# Serial_CAN_Bus_V1_3.net
KiCad netlist of a schematic drawn in EAGLE
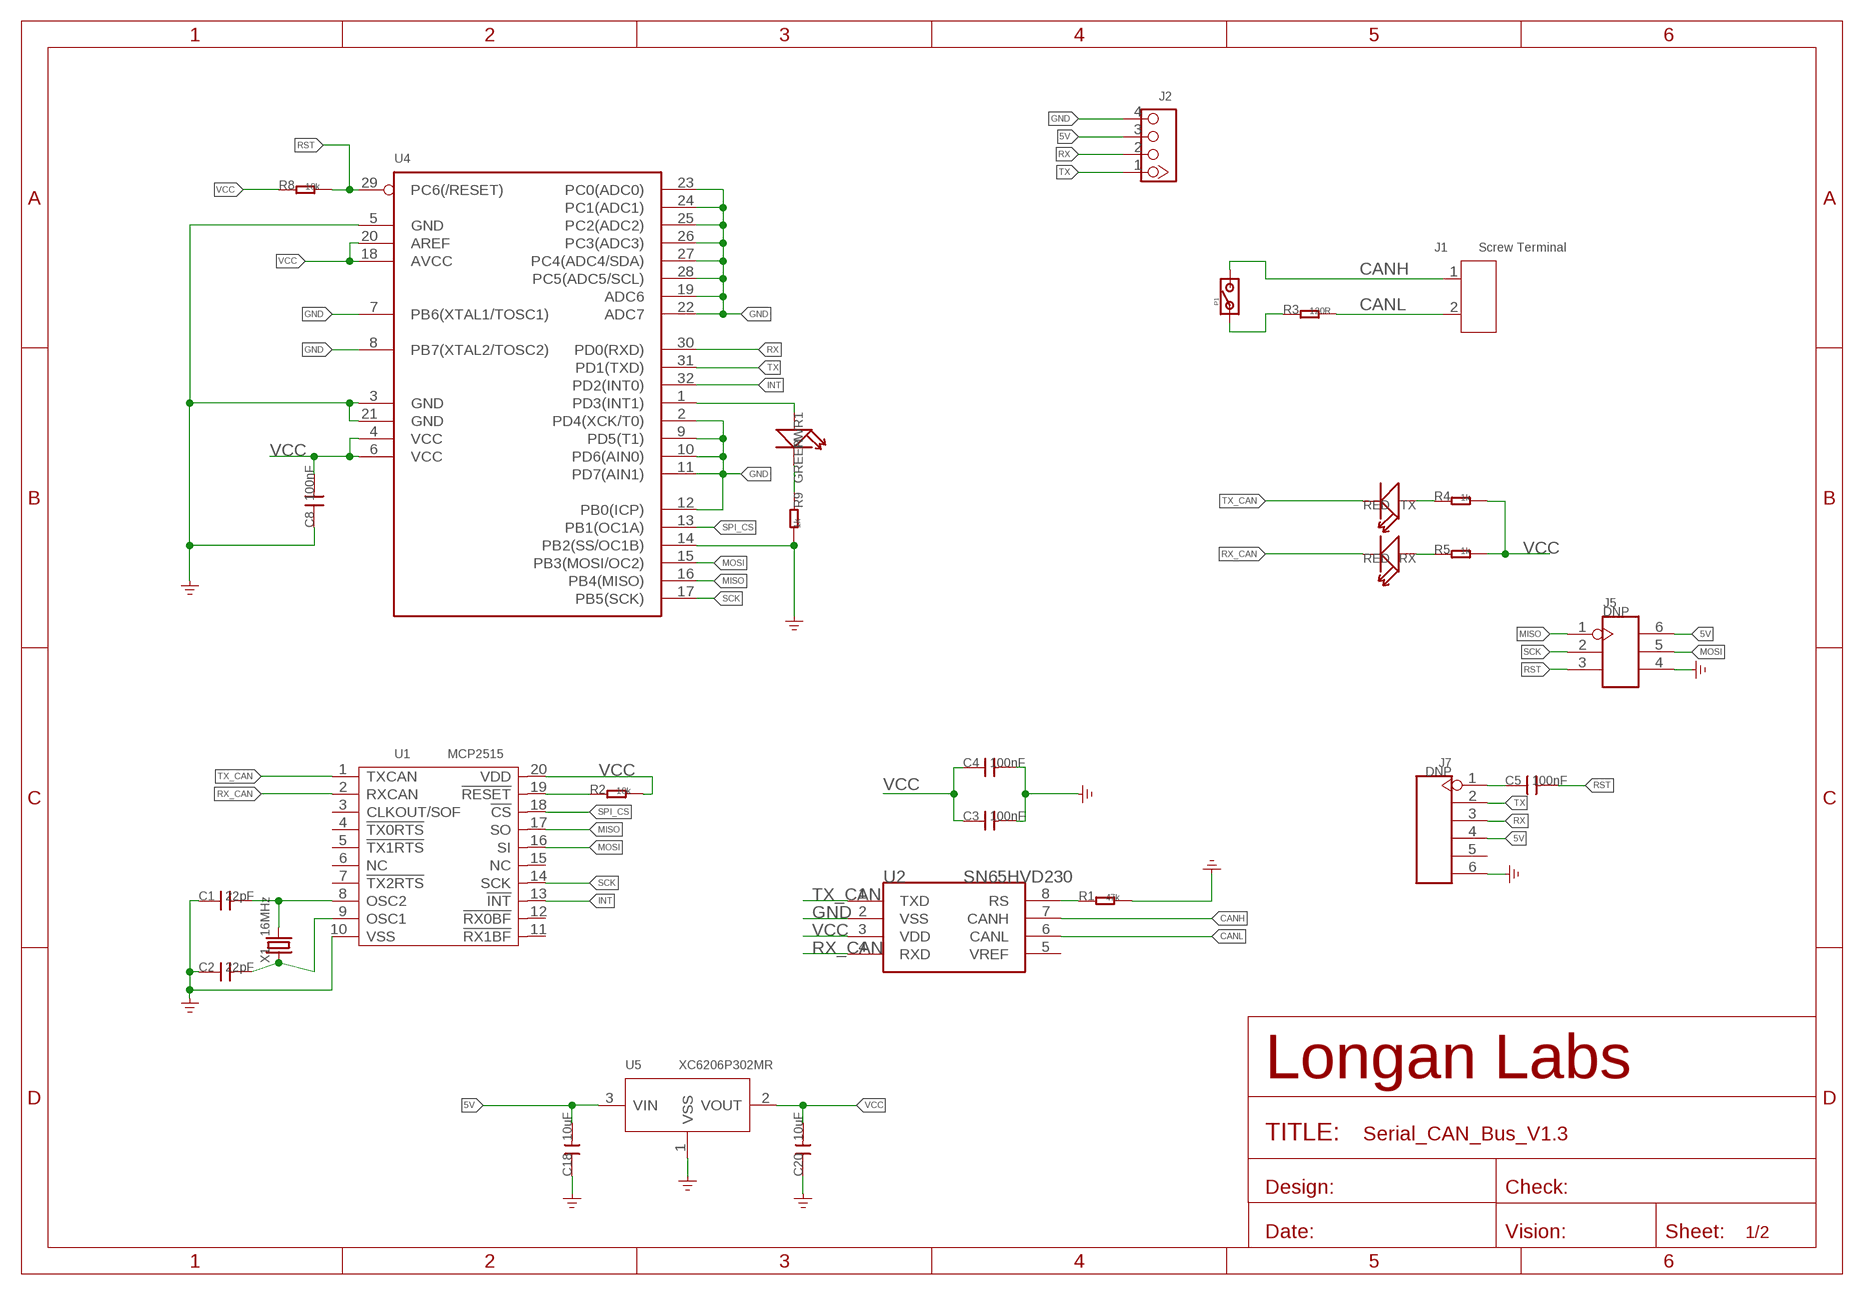
[diagram p0: schematic, sheet 1]

(export (version "E")
  (design (tool "Eeschema 10.0.6"))
  (components
    (comp (ref "C1")
      (value "22pF")
      (footprint "eagle-import:0603")
      (libsource (lib "eagle-import") (part "C-0603"))
    )
    (comp (ref "C2")
      (value "22pF")
      (footprint "eagle-import:0603")
      (libsource (lib "eagle-import") (part "C-0603"))
    )
    (comp (ref "C3")
      (value "100nF")
      (footprint "eagle-import:0603")
      (libsource (lib "eagle-import") (part "C-0603"))
    )
    (comp (ref "C4")
      (value "100nF")
      (footprint "eagle-import:0603")
      (libsource (lib "eagle-import") (part "C-0603"))
    )
    (comp (ref "C5")
      (value "100nF")
      (footprint "eagle-import:0603")
      (libsource (lib "eagle-import") (part "C-0603"))
    )
    (comp (ref "C8")
      (value "100nF")
      (footprint "eagle-import:0603")
      (libsource (lib "eagle-import") (part "C-0603"))
    )
    (comp (ref "C18")
      (value "10uF")
      (footprint "eagle-import:C0603")
      (libsource (lib "eagle-import") (part "CAP-0603"))
    )
    (comp (ref "C20")
      (value "10uF")
      (footprint "eagle-import:C0603")
      (libsource (lib "eagle-import") (part "CAP-0603"))
    )
    (comp (ref "J1")
      (value "Screw Terminal")
      (footprint "eagle-import:2P-3.5")
      (libsource (lib "eagle-import") (part "SCREW-TERMINAL-2P'3.5'"))
    )
    (comp (ref "J2")
      (value "320110033")
      (footprint "eagle-import:HW4-2.0")
      (libsource (lib "eagle-import") (part "GROVE-CONNECTOR-DIP-2.0"))
    )
    (comp (ref "J5")
      (value "DNP")
      (footprint "eagle-import:H2X3-SMD-2.0(1.143)")
      (libsource (lib "eagle-import") (part "HEADER-2X3P-2.0-1.143"))
    )
    (comp (ref "J7")
      (value "DNP")
      (footprint "eagle-import:H6-2.54")
      (libsource (lib "eagle-import") (part "HEADER-6P-55/35MIL"))
    )
    (comp (ref "P1")
      (value "PAD-JUMPER-2P")
      (footprint "eagle-import:2P-SMD-1.78X1.27")
      (libsource (lib "eagle-import") (part "PAD-JUMPER-2P"))
    )
    (comp (ref "PWR1")
      (value "GREEN")
      (footprint "eagle-import:LED-0603")
      (libsource (lib "eagle-import") (part "LED'0603'"))
    )
    (comp (ref "R1")
      (value "47k")
      (footprint "eagle-import:0603")
      (libsource (lib "eagle-import") (part "R-0603"))
    )
    (comp (ref "R2")
      (value "10k")
      (footprint "eagle-import:0603")
      (libsource (lib "eagle-import") (part "R-0603"))
    )
    (comp (ref "R3")
      (value "120R")
      (footprint "eagle-import:0603")
      (libsource (lib "eagle-import") (part "R-0603"))
    )
    (comp (ref "R4")
      (value "1k")
      (footprint "eagle-import:0603")
      (libsource (lib "eagle-import") (part "R-0603"))
    )
    (comp (ref "R5")
      (value "1k")
      (footprint "eagle-import:0603")
      (libsource (lib "eagle-import") (part "R-0603"))
    )
    (comp (ref "R8")
      (value "10k")
      (footprint "eagle-import:0603")
      (libsource (lib "eagle-import") (part "R-0603"))
    )
    (comp (ref "R9")
      (value "1k")
      (footprint "eagle-import:0603")
      (libsource (lib "eagle-import") (part "R-0603"))
    )
    (comp (ref "RX")
      (value "RED")
      (footprint "eagle-import:LED-0603")
      (libsource (lib "eagle-import") (part "LED'0603'"))
    )
    (comp (ref "TX")
      (value "RED")
      (footprint "eagle-import:LED-0603")
      (libsource (lib "eagle-import") (part "LED'0603'"))
    )
    (comp (ref "U1")
      (value "MCP2515")
      (footprint "eagle-import:TSSOP20-0.65-6.5X4.4MM")
      (libsource (lib "eagle-import") (part "MCP2515'ST'"))
    )
    (comp (ref "U2")
      (value "SN65HVD230")
      (footprint "eagle-import:SOIC8-6.0")
      (libsource (lib "eagle-import") (part "MCP2551-SOIC8"))
    )
    (comp (ref "U4")
      (value "MCU-ATMEGA8/168/328'AU'")
      (footprint "eagle-import:TQFP32-0.8-7X7MM")
      (libsource (lib "eagle-import") (part "MCU-ATMEGA8/168/328'AU'"))
    )
    (comp (ref "U5")
      (value "XC6206P302MR")
      (footprint "eagle-import:SOT-23")
      (libsource (lib "eagle-import") (part "PMIC-XC6206PMR"))
    )
    (comp (ref "X1")
      (value "16MHz")
      (footprint "eagle-import:HC49US")
      (libsource (lib "eagle-import") (part "CRYSTAL-2P'HC49US'"))
    )
  )
  (nets
    (net (code "1") (name "5V") (class "Default")
      (node (ref "C18") (pin "2") (pinfunction "2_2") (pintype "passive"))
      (node (ref "J2") (pin "3") (pinfunction "3_3") (pintype "bidirectional"))
      (node (ref "J5") (pin "6") (pinfunction "6_6") (pintype "bidirectional"))
      (node (ref "J7") (pin "4") (pinfunction "4_4") (pintype "bidirectional"))
      (node (ref "U5") (pin "3") (pinfunction "VIN_3") (pintype "bidirectional"))
    )
    (net (code "2") (name "CANH") (class "Default")
      (node (ref "J1") (pin "1") (pinfunction "1_1") (pintype "bidirectional"))
      (node (ref "P1") (pin "2") (pinfunction "2_2") (pintype "bidirectional"))
      (node (ref "U2") (pin "7") (pinfunction "CANH_7") (pintype "bidirectional"))
    )
    (net (code "3") (name "CANL") (class "Default")
      (node (ref "J1") (pin "2") (pinfunction "2_2") (pintype "bidirectional"))
      (node (ref "R3") (pin "2") (pinfunction "2_2") (pintype "passive"))
      (node (ref "U2") (pin "6") (pinfunction "CANL_6") (pintype "bidirectional"))
    )
    (net (code "4") (name "GND") (class "Default")
      (node (ref "C1") (pin "1") (pinfunction "1_1") (pintype "passive"))
      (node (ref "C18") (pin "1") (pinfunction "1_1") (pintype "passive"))
      (node (ref "C2") (pin "1") (pinfunction "1_1") (pintype "passive"))
      (node (ref "C20") (pin "1") (pinfunction "1_1") (pintype "passive"))
      (node (ref "C3") (pin "2") (pinfunction "2_2") (pintype "passive"))
      (node (ref "C4") (pin "2") (pinfunction "2_2") (pintype "passive"))
      (node (ref "C8") (pin "1") (pinfunction "1_1") (pintype "passive"))
      (node (ref "J2") (pin "4") (pinfunction "4_4") (pintype "bidirectional"))
      (node (ref "J5") (pin "4") (pinfunction "4_4") (pintype "bidirectional"))
      (node (ref "J7") (pin "6") (pinfunction "6_6") (pintype "bidirectional"))
      (node (ref "R1") (pin "2") (pinfunction "2_2") (pintype "passive"))
      (node (ref "R9") (pin "2") (pinfunction "2_2") (pintype "passive"))
      (node (ref "U1") (pin "10") (pinfunction "VSS_10") (pintype "bidirectional"))
      (node (ref "U2") (pin "2") (pinfunction "VSS_2") (pintype "bidirectional"))
      (node (ref "U4") (pin "10") (pinfunction "PD6(AIN0)_10") (pintype "bidirectional"))
      (node (ref "U4") (pin "11") (pinfunction "PD7(AIN1)_11") (pintype "bidirectional"))
      (node (ref "U4") (pin "12") (pinfunction "PB0(ICP)_12") (pintype "bidirectional"))
      (node (ref "U4") (pin "14") (pinfunction "PB2(SS/OC1B)_14") (pintype "bidirectional"))
      (node (ref "U4") (pin "19") (pinfunction "ADC6_19") (pintype "bidirectional"))
      (node (ref "U4") (pin "2") (pinfunction "PD4(XCK/T0)_2") (pintype "bidirectional"))
      (node (ref "U4") (pin "21") (pinfunction "GND_21") (pintype "bidirectional"))
      (node (ref "U4") (pin "22") (pinfunction "ADC7_22") (pintype "bidirectional"))
      (node (ref "U4") (pin "23") (pinfunction "PC0(ADC0)_23") (pintype "bidirectional"))
      (node (ref "U4") (pin "24") (pinfunction "PC1(ADC1)_24") (pintype "bidirectional"))
      (node (ref "U4") (pin "25") (pinfunction "PC2(ADC2)_25") (pintype "bidirectional"))
      (node (ref "U4") (pin "26") (pinfunction "PC3(ADC3)_26") (pintype "bidirectional"))
      (node (ref "U4") (pin "27") (pinfunction "PC4(ADC4/SDA)_27") (pintype "bidirectional"))
      (node (ref "U4") (pin "28") (pinfunction "PC5(ADC5/SCL)_28") (pintype "bidirectional"))
      (node (ref "U4") (pin "3") (pinfunction "GND_3") (pintype "bidirectional"))
      (node (ref "U4") (pin "5") (pinfunction "GND_5") (pintype "bidirectional"))
      (node (ref "U4") (pin "7") (pinfunction "PB6(XTAL1/TOSC1)_7") (pintype "bidirectional"))
      (node (ref "U4") (pin "8") (pinfunction "PB7(XTAL2/TOSC2)_8") (pintype "bidirectional"))
      (node (ref "U4") (pin "9") (pinfunction "PD5(T1)_9") (pintype "bidirectional"))
      (node (ref "U5") (pin "1") (pinfunction "VSS_1") (pintype "bidirectional"))
    )
    (net (code "5") (name "INT") (class "Default")
      (node (ref "U1") (pin "13") (pinfunction "~{INT}_13") (pintype "bidirectional"))
      (node (ref "U4") (pin "32") (pinfunction "PD2(INT0)_32") (pintype "bidirectional"))
    )
    (net (code "6") (name "MISO") (class "Default")
      (node (ref "J5") (pin "1") (pinfunction "1_1") (pintype "bidirectional"))
      (node (ref "U1") (pin "17") (pinfunction "SO_17") (pintype "bidirectional"))
      (node (ref "U4") (pin "16") (pinfunction "PB4(MISO)_16") (pintype "bidirectional"))
    )
    (net (code "7") (name "MOSI") (class "Default")
      (node (ref "J5") (pin "5") (pinfunction "5_5") (pintype "bidirectional"))
      (node (ref "U1") (pin "16") (pinfunction "SI_16") (pintype "bidirectional"))
      (node (ref "U4") (pin "15") (pinfunction "PB3(MOSI/OC2)_15") (pintype "bidirectional"))
    )
    (net (code "8") (name "Net-(C5-Pad1)") (class "Default")
      (node (ref "C5") (pin "1") (pinfunction "1_1") (pintype "passive"))
      (node (ref "J7") (pin "1") (pinfunction "1_1") (pintype "bidirectional"))
    )
    (net (code "9") (name "Net-(P1-Pad1)") (class "Default")
      (node (ref "P1") (pin "1") (pinfunction "1_1") (pintype "bidirectional"))
      (node (ref "R3") (pin "1") (pinfunction "1_1") (pintype "passive"))
    )
    (net (code "10") (name "Net-(PWR1-Pad-)") (class "Default")
      (node (ref "PWR1") (pin "-") (pinfunction "-_-") (pintype "passive"))
      (node (ref "R9") (pin "1") (pinfunction "1_1") (pintype "passive"))
    )
    (net (code "11") (name "Net-(R4-Pad1)") (class "Default")
      (node (ref "R4") (pin "1") (pinfunction "1_1") (pintype "passive"))
      (node (ref "TX") (pin "+") (pinfunction "+_+") (pintype "passive"))
    )
    (net (code "12") (name "Net-(R5-Pad1)") (class "Default")
      (node (ref "R5") (pin "1") (pinfunction "1_1") (pintype "passive"))
      (node (ref "RX") (pin "+") (pinfunction "+_+") (pintype "passive"))
    )
    (net (code "13") (name "Net-(U1-OSC1)") (class "Default")
      (node (ref "C2") (pin "2") (pinfunction "2_2") (pintype "passive"))
      (node (ref "U1") (pin "9") (pinfunction "OSC1_9") (pintype "bidirectional"))
      (node (ref "X1") (pin "1") (pinfunction "1_1") (pintype "passive"))
    )
    (net (code "14") (name "Net-(U1-OSC2)") (class "Default")
      (node (ref "C1") (pin "2") (pinfunction "2_2") (pintype "passive"))
      (node (ref "U1") (pin "8") (pinfunction "OSC2_8") (pintype "bidirectional"))
      (node (ref "X1") (pin "2") (pinfunction "2_2") (pintype "passive"))
    )
    (net (code "15") (name "Net-(U1-~{RESET})") (class "Default")
      (node (ref "R2") (pin "1") (pinfunction "1_1") (pintype "passive"))
      (node (ref "U1") (pin "19") (pinfunction "~{RESET}_19") (pintype "bidirectional"))
    )
    (net (code "16") (name "Net-(U2-RS)") (class "Default")
      (node (ref "R1") (pin "1") (pinfunction "1_1") (pintype "passive"))
      (node (ref "U2") (pin "8") (pinfunction "RS_8") (pintype "bidirectional"))
    )
    (net (code "17") (name "Net-(U4-PD3(INT1))") (class "Default")
      (node (ref "PWR1") (pin "+") (pinfunction "+_+") (pintype "passive"))
      (node (ref "U4") (pin "1") (pinfunction "PD3(INT1)_1") (pintype "bidirectional"))
    )
    (net (code "18") (name "RST") (class "Default")
      (node (ref "C5") (pin "2") (pinfunction "2_2") (pintype "passive"))
      (node (ref "J5") (pin "3") (pinfunction "3_3") (pintype "bidirectional"))
      (node (ref "R8") (pin "2") (pinfunction "2_2") (pintype "passive"))
      (node (ref "U4") (pin "29") (pinfunction "PC6(/RESET)_29") (pintype "bidirectional"))
    )
    (net (code "19") (name "RX") (class "Default")
      (node (ref "J2") (pin "2") (pinfunction "2_2") (pintype "bidirectional"))
      (node (ref "J7") (pin "3") (pinfunction "3_3") (pintype "bidirectional"))
      (node (ref "U4") (pin "30") (pinfunction "PD0(RXD)_30") (pintype "bidirectional"))
    )
    (net (code "20") (name "RX_CAN") (class "Default")
      (node (ref "RX") (pin "-") (pinfunction "-_-") (pintype "passive"))
      (node (ref "U1") (pin "2") (pinfunction "RXCAN_2") (pintype "bidirectional"))
      (node (ref "U2") (pin "4") (pinfunction "RXD_4") (pintype "bidirectional"))
    )
    (net (code "21") (name "SCK") (class "Default")
      (node (ref "J5") (pin "2") (pinfunction "2_2") (pintype "bidirectional"))
      (node (ref "U1") (pin "14") (pinfunction "SCK_14") (pintype "bidirectional"))
      (node (ref "U4") (pin "17") (pinfunction "PB5(SCK)_17") (pintype "bidirectional"))
    )
    (net (code "22") (name "SPI_CS") (class "Default")
      (node (ref "U1") (pin "18") (pinfunction "~{CS}_18") (pintype "bidirectional"))
      (node (ref "U4") (pin "13") (pinfunction "PB1(OC1A)_13") (pintype "bidirectional"))
    )
    (net (code "23") (name "TX") (class "Default")
      (node (ref "J2") (pin "1") (pinfunction "1_1") (pintype "bidirectional"))
      (node (ref "J7") (pin "2") (pinfunction "2_2") (pintype "bidirectional"))
      (node (ref "U4") (pin "31") (pinfunction "PD1(TXD)_31") (pintype "bidirectional"))
    )
    (net (code "24") (name "TX_CAN") (class "Default")
      (node (ref "TX") (pin "-") (pinfunction "-_-") (pintype "passive"))
      (node (ref "U1") (pin "1") (pinfunction "TXCAN_1") (pintype "bidirectional"))
      (node (ref "U2") (pin "1") (pinfunction "TXD_1") (pintype "bidirectional"))
    )
    (net (code "25") (name "VCC") (class "Default")
      (node (ref "C20") (pin "2") (pinfunction "2_2") (pintype "passive"))
      (node (ref "C3") (pin "1") (pinfunction "1_1") (pintype "passive"))
      (node (ref "C4") (pin "1") (pinfunction "1_1") (pintype "passive"))
      (node (ref "C8") (pin "2") (pinfunction "2_2") (pintype "passive"))
      (node (ref "R2") (pin "2") (pinfunction "2_2") (pintype "passive"))
      (node (ref "R4") (pin "2") (pinfunction "2_2") (pintype "passive"))
      (node (ref "R5") (pin "2") (pinfunction "2_2") (pintype "passive"))
      (node (ref "R8") (pin "1") (pinfunction "1_1") (pintype "passive"))
      (node (ref "U1") (pin "20") (pinfunction "VDD_20") (pintype "bidirectional"))
      (node (ref "U2") (pin "3") (pinfunction "VDD_3") (pintype "bidirectional"))
      (node (ref "U4") (pin "18") (pinfunction "AVCC_18") (pintype "bidirectional"))
      (node (ref "U4") (pin "20") (pinfunction "AREF_20") (pintype "bidirectional"))
      (node (ref "U4") (pin "4") (pinfunction "VCC_4") (pintype "bidirectional"))
      (node (ref "U4") (pin "6") (pinfunction "VCC_6") (pintype "bidirectional"))
      (node (ref "U5") (pin "2") (pinfunction "VOUT_2") (pintype "bidirectional"))
    )
    (net (code "26") (name "unconnected-(J7-Pad5)") (class "Default")
      (node (ref "J7") (pin "5") (pinfunction "5_5") (pintype "bidirectional"))
    )
    (net (code "27") (name "unconnected-(U1-CLKOUT{slash}SOF-Pad3)") (class "Default")
      (node (ref "U1") (pin "3") (pinfunction "CLKOUT/SOF_3") (pintype "bidirectional"))
    )
    (net (code "28") (name "unconnected-(U1-NC-Pad6)") (class "Default")
      (node (ref "U1") (pin "6") (pinfunction "NC_6") (pintype "bidirectional"))
    )
    (net (code "29") (name "unconnected-(U1-NC-Pad15)") (class "Default")
      (node (ref "U1") (pin "15") (pinfunction "NC_15") (pintype "bidirectional"))
    )
    (net (code "30") (name "unconnected-(U1-~{RX0BF}-Pad12)") (class "Default")
      (node (ref "U1") (pin "12") (pinfunction "~{RX0BF}_12") (pintype "bidirectional"))
    )
    (net (code "31") (name "unconnected-(U1-~{RX1BF}-Pad11)") (class "Default")
      (node (ref "U1") (pin "11") (pinfunction "~{RX1BF}_11") (pintype "bidirectional"))
    )
    (net (code "32") (name "unconnected-(U1-~{TX0RTS}-Pad4)") (class "Default")
      (node (ref "U1") (pin "4") (pinfunction "~{TX0RTS}_4") (pintype "bidirectional"))
    )
    (net (code "33") (name "unconnected-(U1-~{TX1RTS}-Pad5)") (class "Default")
      (node (ref "U1") (pin "5") (pinfunction "~{TX1RTS}_5") (pintype "bidirectional"))
    )
    (net (code "34") (name "unconnected-(U1-~{TX2RTS}-Pad7)") (class "Default")
      (node (ref "U1") (pin "7") (pinfunction "~{TX2RTS}_7") (pintype "bidirectional"))
    )
    (net (code "35") (name "unconnected-(U2-VREF-Pad5)") (class "Default")
      (node (ref "U2") (pin "5") (pinfunction "VREF_5") (pintype "bidirectional"))
    )
  )
)
